# Debug_Phantom.net
KiCad netlist of a schematic drawn in EAGLE
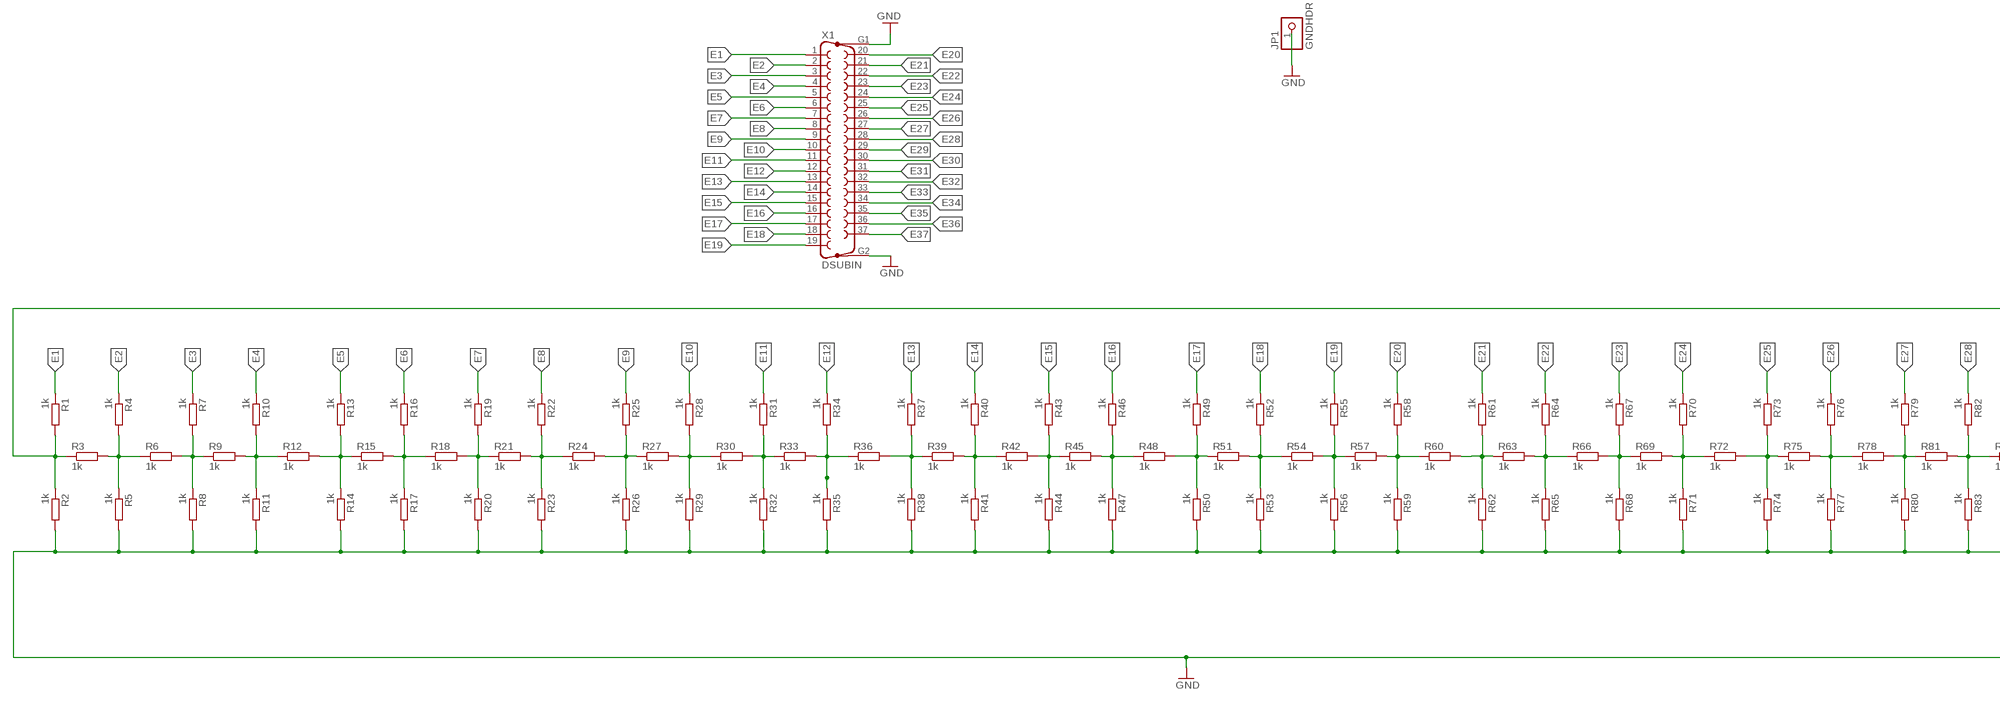
[diagram p0: schematic, sheet 1, part 1 of 2]
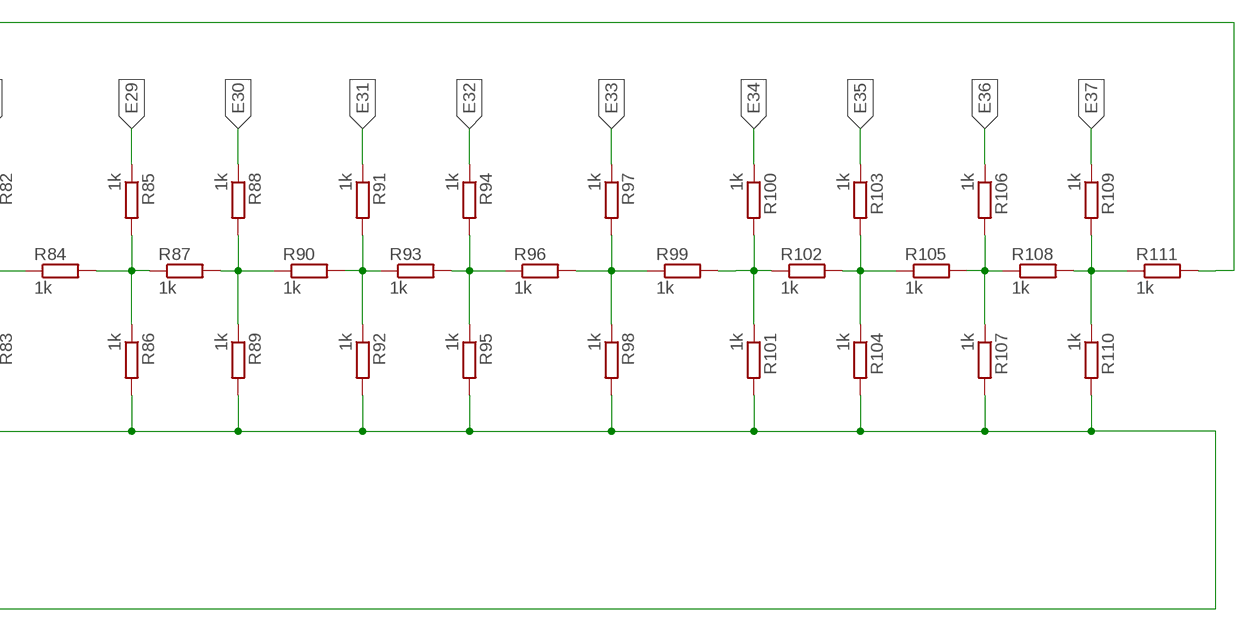
[diagram p1: schematic, sheet 1, part 2 of 2]

(export (version "E")
  (design (tool "Eeschema 10.0.6"))
  (components
    (comp (ref "JP1")
      (value "GNDHDR")
      (footprint "eagle-import:1X01")
      (libsource (lib "eagle-import") (part "PINHD-1X1"))
    )
    (comp (ref "R1")
      (value "1k")
      (footprint "eagle-import:R0402")
      (libsource (lib "eagle-import") (part "R-EU_R0402"))
    )
    (comp (ref "R2")
      (value "1k")
      (footprint "eagle-import:R0402")
      (libsource (lib "eagle-import") (part "R-EU_R0402"))
    )
    (comp (ref "R3")
      (value "1k")
      (footprint "eagle-import:R0402")
      (libsource (lib "eagle-import") (part "R-EU_R0402"))
    )
    (comp (ref "R4")
      (value "1k")
      (footprint "eagle-import:R0402")
      (libsource (lib "eagle-import") (part "R-EU_R0402"))
    )
    (comp (ref "R5")
      (value "1k")
      (footprint "eagle-import:R0402")
      (libsource (lib "eagle-import") (part "R-EU_R0402"))
    )
    (comp (ref "R6")
      (value "1k")
      (footprint "eagle-import:R0402")
      (libsource (lib "eagle-import") (part "R-EU_R0402"))
    )
    (comp (ref "R7")
      (value "1k")
      (footprint "eagle-import:R0402")
      (libsource (lib "eagle-import") (part "R-EU_R0402"))
    )
    (comp (ref "R8")
      (value "1k")
      (footprint "eagle-import:R0402")
      (libsource (lib "eagle-import") (part "R-EU_R0402"))
    )
    (comp (ref "R9")
      (value "1k")
      (footprint "eagle-import:R0402")
      (libsource (lib "eagle-import") (part "R-EU_R0402"))
    )
    (comp (ref "R10")
      (value "1k")
      (footprint "eagle-import:R0402")
      (libsource (lib "eagle-import") (part "R-EU_R0402"))
    )
    (comp (ref "R11")
      (value "1k")
      (footprint "eagle-import:R0402")
      (libsource (lib "eagle-import") (part "R-EU_R0402"))
    )
    (comp (ref "R12")
      (value "1k")
      (footprint "eagle-import:R0402")
      (libsource (lib "eagle-import") (part "R-EU_R0402"))
    )
    (comp (ref "R13")
      (value "1k")
      (footprint "eagle-import:R0402")
      (libsource (lib "eagle-import") (part "R-EU_R0402"))
    )
    (comp (ref "R14")
      (value "1k")
      (footprint "eagle-import:R0402")
      (libsource (lib "eagle-import") (part "R-EU_R0402"))
    )
    (comp (ref "R15")
      (value "1k")
      (footprint "eagle-import:R0402")
      (libsource (lib "eagle-import") (part "R-EU_R0402"))
    )
    (comp (ref "R16")
      (value "1k")
      (footprint "eagle-import:R0402")
      (libsource (lib "eagle-import") (part "R-EU_R0402"))
    )
    (comp (ref "R17")
      (value "1k")
      (footprint "eagle-import:R0402")
      (libsource (lib "eagle-import") (part "R-EU_R0402"))
    )
    (comp (ref "R18")
      (value "1k")
      (footprint "eagle-import:R0402")
      (libsource (lib "eagle-import") (part "R-EU_R0402"))
    )
    (comp (ref "R19")
      (value "1k")
      (footprint "eagle-import:R0402")
      (libsource (lib "eagle-import") (part "R-EU_R0402"))
    )
    (comp (ref "R20")
      (value "1k")
      (footprint "eagle-import:R0402")
      (libsource (lib "eagle-import") (part "R-EU_R0402"))
    )
    (comp (ref "R21")
      (value "1k")
      (footprint "eagle-import:R0402")
      (libsource (lib "eagle-import") (part "R-EU_R0402"))
    )
    (comp (ref "R22")
      (value "1k")
      (footprint "eagle-import:R0402")
      (libsource (lib "eagle-import") (part "R-EU_R0402"))
    )
    (comp (ref "R23")
      (value "1k")
      (footprint "eagle-import:R0402")
      (libsource (lib "eagle-import") (part "R-EU_R0402"))
    )
    (comp (ref "R24")
      (value "1k")
      (footprint "eagle-import:R0402")
      (libsource (lib "eagle-import") (part "R-EU_R0402"))
    )
    (comp (ref "R25")
      (value "1k")
      (footprint "eagle-import:R0402")
      (libsource (lib "eagle-import") (part "R-EU_R0402"))
    )
    (comp (ref "R26")
      (value "1k")
      (footprint "eagle-import:R0402")
      (libsource (lib "eagle-import") (part "R-EU_R0402"))
    )
    (comp (ref "R27")
      (value "1k")
      (footprint "eagle-import:R0402")
      (libsource (lib "eagle-import") (part "R-EU_R0402"))
    )
    (comp (ref "R28")
      (value "1k")
      (footprint "eagle-import:R0402")
      (libsource (lib "eagle-import") (part "R-EU_R0402"))
    )
    (comp (ref "R29")
      (value "1k")
      (footprint "eagle-import:R0402")
      (libsource (lib "eagle-import") (part "R-EU_R0402"))
    )
    (comp (ref "R30")
      (value "1k")
      (footprint "eagle-import:R0402")
      (libsource (lib "eagle-import") (part "R-EU_R0402"))
    )
    (comp (ref "R31")
      (value "1k")
      (footprint "eagle-import:R0402")
      (libsource (lib "eagle-import") (part "R-EU_R0402"))
    )
    (comp (ref "R32")
      (value "1k")
      (footprint "eagle-import:R0402")
      (libsource (lib "eagle-import") (part "R-EU_R0402"))
    )
    (comp (ref "R33")
      (value "1k")
      (footprint "eagle-import:R0402")
      (libsource (lib "eagle-import") (part "R-EU_R0402"))
    )
    (comp (ref "R34")
      (value "1k")
      (footprint "eagle-import:R0402")
      (libsource (lib "eagle-import") (part "R-EU_R0402"))
    )
    (comp (ref "R35")
      (value "1k")
      (footprint "eagle-import:R0402")
      (libsource (lib "eagle-import") (part "R-EU_R0402"))
    )
    (comp (ref "R36")
      (value "1k")
      (footprint "eagle-import:R0402")
      (libsource (lib "eagle-import") (part "R-EU_R0402"))
    )
    (comp (ref "R37")
      (value "1k")
      (footprint "eagle-import:R0402")
      (libsource (lib "eagle-import") (part "R-EU_R0402"))
    )
    (comp (ref "R38")
      (value "1k")
      (footprint "eagle-import:R0402")
      (libsource (lib "eagle-import") (part "R-EU_R0402"))
    )
    (comp (ref "R39")
      (value "1k")
      (footprint "eagle-import:R0402")
      (libsource (lib "eagle-import") (part "R-EU_R0402"))
    )
    (comp (ref "R40")
      (value "1k")
      (footprint "eagle-import:R0402")
      (libsource (lib "eagle-import") (part "R-EU_R0402"))
    )
    (comp (ref "R41")
      (value "1k")
      (footprint "eagle-import:R0402")
      (libsource (lib "eagle-import") (part "R-EU_R0402"))
    )
    (comp (ref "R42")
      (value "1k")
      (footprint "eagle-import:R0402")
      (libsource (lib "eagle-import") (part "R-EU_R0402"))
    )
    (comp (ref "R43")
      (value "1k")
      (footprint "eagle-import:R0402")
      (libsource (lib "eagle-import") (part "R-EU_R0402"))
    )
    (comp (ref "R44")
      (value "1k")
      (footprint "eagle-import:R0402")
      (libsource (lib "eagle-import") (part "R-EU_R0402"))
    )
    (comp (ref "R45")
      (value "1k")
      (footprint "eagle-import:R0402")
      (libsource (lib "eagle-import") (part "R-EU_R0402"))
    )
    (comp (ref "R46")
      (value "1k")
      (footprint "eagle-import:R0402")
      (libsource (lib "eagle-import") (part "R-EU_R0402"))
    )
    (comp (ref "R47")
      (value "1k")
      (footprint "eagle-import:R0402")
      (libsource (lib "eagle-import") (part "R-EU_R0402"))
    )
    (comp (ref "R48")
      (value "1k")
      (footprint "eagle-import:R0402")
      (libsource (lib "eagle-import") (part "R-EU_R0402"))
    )
    (comp (ref "R49")
      (value "1k")
      (footprint "eagle-import:R0402")
      (libsource (lib "eagle-import") (part "R-EU_R0402"))
    )
    (comp (ref "R50")
      (value "1k")
      (footprint "eagle-import:R0402")
      (libsource (lib "eagle-import") (part "R-EU_R0402"))
    )
    (comp (ref "R51")
      (value "1k")
      (footprint "eagle-import:R0402")
      (libsource (lib "eagle-import") (part "R-EU_R0402"))
    )
    (comp (ref "R52")
      (value "1k")
      (footprint "eagle-import:R0402")
      (libsource (lib "eagle-import") (part "R-EU_R0402"))
    )
    (comp (ref "R53")
      (value "1k")
      (footprint "eagle-import:R0402")
      (libsource (lib "eagle-import") (part "R-EU_R0402"))
    )
    (comp (ref "R54")
      (value "1k")
      (footprint "eagle-import:R0402")
      (libsource (lib "eagle-import") (part "R-EU_R0402"))
    )
    (comp (ref "R55")
      (value "1k")
      (footprint "eagle-import:R0402")
      (libsource (lib "eagle-import") (part "R-EU_R0402"))
    )
    (comp (ref "R56")
      (value "1k")
      (footprint "eagle-import:R0402")
      (libsource (lib "eagle-import") (part "R-EU_R0402"))
    )
    (comp (ref "R57")
      (value "1k")
      (footprint "eagle-import:R0402")
      (libsource (lib "eagle-import") (part "R-EU_R0402"))
    )
    (comp (ref "R58")
      (value "1k")
      (footprint "eagle-import:R0402")
      (libsource (lib "eagle-import") (part "R-EU_R0402"))
    )
    (comp (ref "R59")
      (value "1k")
      (footprint "eagle-import:R0402")
      (libsource (lib "eagle-import") (part "R-EU_R0402"))
    )
    (comp (ref "R60")
      (value "1k")
      (footprint "eagle-import:R0402")
      (libsource (lib "eagle-import") (part "R-EU_R0402"))
    )
    (comp (ref "R61")
      (value "1k")
      (footprint "eagle-import:R0402")
      (libsource (lib "eagle-import") (part "R-EU_R0402"))
    )
    (comp (ref "R62")
      (value "1k")
      (footprint "eagle-import:R0402")
      (libsource (lib "eagle-import") (part "R-EU_R0402"))
    )
    (comp (ref "R63")
      (value "1k")
      (footprint "eagle-import:R0402")
      (libsource (lib "eagle-import") (part "R-EU_R0402"))
    )
    (comp (ref "R64")
      (value "1k")
      (footprint "eagle-import:R0402")
      (libsource (lib "eagle-import") (part "R-EU_R0402"))
    )
    (comp (ref "R65")
      (value "1k")
      (footprint "eagle-import:R0402")
      (libsource (lib "eagle-import") (part "R-EU_R0402"))
    )
    (comp (ref "R66")
      (value "1k")
      (footprint "eagle-import:R0402")
      (libsource (lib "eagle-import") (part "R-EU_R0402"))
    )
    (comp (ref "R67")
      (value "1k")
      (footprint "eagle-import:R0402")
      (libsource (lib "eagle-import") (part "R-EU_R0402"))
    )
    (comp (ref "R68")
      (value "1k")
      (footprint "eagle-import:R0402")
      (libsource (lib "eagle-import") (part "R-EU_R0402"))
    )
    (comp (ref "R69")
      (value "1k")
      (footprint "eagle-import:R0402")
      (libsource (lib "eagle-import") (part "R-EU_R0402"))
    )
    (comp (ref "R70")
      (value "1k")
      (footprint "eagle-import:R0402")
      (libsource (lib "eagle-import") (part "R-EU_R0402"))
    )
    (comp (ref "R71")
      (value "1k")
      (footprint "eagle-import:R0402")
      (libsource (lib "eagle-import") (part "R-EU_R0402"))
    )
    (comp (ref "R72")
      (value "1k")
      (footprint "eagle-import:R0402")
      (libsource (lib "eagle-import") (part "R-EU_R0402"))
    )
    (comp (ref "R73")
      (value "1k")
      (footprint "eagle-import:R0402")
      (libsource (lib "eagle-import") (part "R-EU_R0402"))
    )
    (comp (ref "R74")
      (value "1k")
      (footprint "eagle-import:R0402")
      (libsource (lib "eagle-import") (part "R-EU_R0402"))
    )
    (comp (ref "R75")
      (value "1k")
      (footprint "eagle-import:R0402")
      (libsource (lib "eagle-import") (part "R-EU_R0402"))
    )
    (comp (ref "R76")
      (value "1k")
      (footprint "eagle-import:R0402")
      (libsource (lib "eagle-import") (part "R-EU_R0402"))
    )
    (comp (ref "R77")
      (value "1k")
      (footprint "eagle-import:R0402")
      (libsource (lib "eagle-import") (part "R-EU_R0402"))
    )
    (comp (ref "R78")
      (value "1k")
      (footprint "eagle-import:R0402")
      (libsource (lib "eagle-import") (part "R-EU_R0402"))
    )
    (comp (ref "R79")
      (value "1k")
      (footprint "eagle-import:R0402")
      (libsource (lib "eagle-import") (part "R-EU_R0402"))
    )
    (comp (ref "R80")
      (value "1k")
      (footprint "eagle-import:R0402")
      (libsource (lib "eagle-import") (part "R-EU_R0402"))
    )
    (comp (ref "R81")
      (value "1k")
      (footprint "eagle-import:R0402")
      (libsource (lib "eagle-import") (part "R-EU_R0402"))
    )
    (comp (ref "R82")
      (value "1k")
      (footprint "eagle-import:R0402")
      (libsource (lib "eagle-import") (part "R-EU_R0402"))
    )
    (comp (ref "R83")
      (value "1k")
      (footprint "eagle-import:R0402")
      (libsource (lib "eagle-import") (part "R-EU_R0402"))
    )
    (comp (ref "R84")
      (value "1k")
      (footprint "eagle-import:R0402")
      (libsource (lib "eagle-import") (part "R-EU_R0402"))
    )
    (comp (ref "R85")
      (value "1k")
      (footprint "eagle-import:R0402")
      (libsource (lib "eagle-import") (part "R-EU_R0402"))
    )
    (comp (ref "R86")
      (value "1k")
      (footprint "eagle-import:R0402")
      (libsource (lib "eagle-import") (part "R-EU_R0402"))
    )
    (comp (ref "R87")
      (value "1k")
      (footprint "eagle-import:R0402")
      (libsource (lib "eagle-import") (part "R-EU_R0402"))
    )
    (comp (ref "R88")
      (value "1k")
      (footprint "eagle-import:R0402")
      (libsource (lib "eagle-import") (part "R-EU_R0402"))
    )
    (comp (ref "R89")
      (value "1k")
      (footprint "eagle-import:R0402")
      (libsource (lib "eagle-import") (part "R-EU_R0402"))
    )
    (comp (ref "R90")
      (value "1k")
      (footprint "eagle-import:R0402")
      (libsource (lib "eagle-import") (part "R-EU_R0402"))
    )
    (comp (ref "R91")
      (value "1k")
      (footprint "eagle-import:R0402")
      (libsource (lib "eagle-import") (part "R-EU_R0402"))
    )
    (comp (ref "R92")
      (value "1k")
      (footprint "eagle-import:R0402")
      (libsource (lib "eagle-import") (part "R-EU_R0402"))
    )
    (comp (ref "R93")
      (value "1k")
      (footprint "eagle-import:R0402")
      (libsource (lib "eagle-import") (part "R-EU_R0402"))
    )
    (comp (ref "R94")
      (value "1k")
      (footprint "eagle-import:R0402")
      (libsource (lib "eagle-import") (part "R-EU_R0402"))
    )
    (comp (ref "R95")
      (value "1k")
      (footprint "eagle-import:R0402")
      (libsource (lib "eagle-import") (part "R-EU_R0402"))
    )
    (comp (ref "R96")
      (value "1k")
      (footprint "eagle-import:R0402")
      (libsource (lib "eagle-import") (part "R-EU_R0402"))
    )
    (comp (ref "R97")
      (value "1k")
      (footprint "eagle-import:R0402")
      (libsource (lib "eagle-import") (part "R-EU_R0402"))
    )
    (comp (ref "R98")
      (value "1k")
      (footprint "eagle-import:R0402")
      (libsource (lib "eagle-import") (part "R-EU_R0402"))
    )
    (comp (ref "R99")
      (value "1k")
      (footprint "eagle-import:R0402")
      (libsource (lib "eagle-import") (part "R-EU_R0402"))
    )
    (comp (ref "R100")
      (value "1k")
      (footprint "eagle-import:R0402")
      (libsource (lib "eagle-import") (part "R-EU_R0402"))
    )
    (comp (ref "R101")
      (value "1k")
      (footprint "eagle-import:R0402")
      (libsource (lib "eagle-import") (part "R-EU_R0402"))
    )
    (comp (ref "R102")
      (value "1k")
      (footprint "eagle-import:R0402")
      (libsource (lib "eagle-import") (part "R-EU_R0402"))
    )
    (comp (ref "R103")
      (value "1k")
      (footprint "eagle-import:R0402")
      (libsource (lib "eagle-import") (part "R-EU_R0402"))
    )
    (comp (ref "R104")
      (value "1k")
      (footprint "eagle-import:R0402")
      (libsource (lib "eagle-import") (part "R-EU_R0402"))
    )
    (comp (ref "R105")
      (value "1k")
      (footprint "eagle-import:R0402")
      (libsource (lib "eagle-import") (part "R-EU_R0402"))
    )
    (comp (ref "R106")
      (value "1k")
      (footprint "eagle-import:R0402")
      (libsource (lib "eagle-import") (part "R-EU_R0402"))
    )
    (comp (ref "R107")
      (value "1k")
      (footprint "eagle-import:R0402")
      (libsource (lib "eagle-import") (part "R-EU_R0402"))
    )
    (comp (ref "R108")
      (value "1k")
      (footprint "eagle-import:R0402")
      (libsource (lib "eagle-import") (part "R-EU_R0402"))
    )
    (comp (ref "R109")
      (value "1k")
      (footprint "eagle-import:R0402")
      (libsource (lib "eagle-import") (part "R-EU_R0402"))
    )
    (comp (ref "R110")
      (value "1k")
      (footprint "eagle-import:R0402")
      (libsource (lib "eagle-import") (part "R-EU_R0402"))
    )
    (comp (ref "R111")
      (value "1k")
      (footprint "eagle-import:R0402")
      (libsource (lib "eagle-import") (part "R-EU_R0402"))
    )
    (comp (ref "X1")
      (value "DSUBIN")
      (footprint "eagle-import:F37VP")
      (libsource (lib "eagle-import") (part "F37VP"))
    )
  )
  (nets
    (net (code "1") (name "E1") (class "Default")
      (node (ref "R1") (pin "1") (pinfunction "1_1") (pintype "passive"))
      (node (ref "X1") (pin "1") (pinfunction "1_1") (pintype "passive"))
    )
    (net (code "2") (name "E2") (class "Default")
      (node (ref "R4") (pin "1") (pinfunction "1_1") (pintype "passive"))
      (node (ref "X1") (pin "2") (pinfunction "2_2") (pintype "passive"))
    )
    (net (code "3") (name "E3") (class "Default")
      (node (ref "R7") (pin "1") (pinfunction "1_1") (pintype "passive"))
      (node (ref "X1") (pin "3") (pinfunction "3_3") (pintype "passive"))
    )
    (net (code "4") (name "E4") (class "Default")
      (node (ref "R10") (pin "1") (pinfunction "1_1") (pintype "passive"))
      (node (ref "X1") (pin "4") (pinfunction "4_4") (pintype "passive"))
    )
    (net (code "5") (name "E5") (class "Default")
      (node (ref "R13") (pin "1") (pinfunction "1_1") (pintype "passive"))
      (node (ref "X1") (pin "5") (pinfunction "5_5") (pintype "passive"))
    )
    (net (code "6") (name "E6") (class "Default")
      (node (ref "R16") (pin "1") (pinfunction "1_1") (pintype "passive"))
      (node (ref "X1") (pin "6") (pinfunction "6_6") (pintype "passive"))
    )
    (net (code "7") (name "E7") (class "Default")
      (node (ref "R19") (pin "1") (pinfunction "1_1") (pintype "passive"))
      (node (ref "X1") (pin "7") (pinfunction "7_7") (pintype "passive"))
    )
    (net (code "8") (name "E8") (class "Default")
      (node (ref "R22") (pin "1") (pinfunction "1_1") (pintype "passive"))
      (node (ref "X1") (pin "8") (pinfunction "8_8") (pintype "passive"))
    )
    (net (code "9") (name "E9") (class "Default")
      (node (ref "R25") (pin "1") (pinfunction "1_1") (pintype "passive"))
      (node (ref "X1") (pin "9") (pinfunction "9_9") (pintype "passive"))
    )
    (net (code "10") (name "E10") (class "Default")
      (node (ref "R28") (pin "1") (pinfunction "1_1") (pintype "passive"))
      (node (ref "X1") (pin "10") (pinfunction "10_10") (pintype "passive"))
    )
    (net (code "11") (name "E11") (class "Default")
      (node (ref "R31") (pin "1") (pinfunction "1_1") (pintype "passive"))
      (node (ref "X1") (pin "11") (pinfunction "11_11") (pintype "passive"))
    )
    (net (code "12") (name "E12") (class "Default")
      (node (ref "R34") (pin "1") (pinfunction "1_1") (pintype "passive"))
      (node (ref "X1") (pin "12") (pinfunction "12_12") (pintype "passive"))
    )
    (net (code "13") (name "E13") (class "Default")
      (node (ref "R37") (pin "1") (pinfunction "1_1") (pintype "passive"))
      (node (ref "X1") (pin "13") (pinfunction "13_13") (pintype "passive"))
    )
    (net (code "14") (name "E14") (class "Default")
      (node (ref "R40") (pin "1") (pinfunction "1_1") (pintype "passive"))
      (node (ref "X1") (pin "14") (pinfunction "14_14") (pintype "passive"))
    )
    (net (code "15") (name "E15") (class "Default")
      (node (ref "R43") (pin "1") (pinfunction "1_1") (pintype "passive"))
      (node (ref "X1") (pin "15") (pinfunction "15_15") (pintype "passive"))
    )
    (net (code "16") (name "E16") (class "Default")
      (node (ref "R46") (pin "1") (pinfunction "1_1") (pintype "passive"))
      (node (ref "X1") (pin "16") (pinfunction "16_16") (pintype "passive"))
    )
    (net (code "17") (name "E17") (class "Default")
      (node (ref "R49") (pin "1") (pinfunction "1_1") (pintype "passive"))
      (node (ref "X1") (pin "17") (pinfunction "17_17") (pintype "passive"))
    )
    (net (code "18") (name "E18") (class "Default")
      (node (ref "R52") (pin "1") (pinfunction "1_1") (pintype "passive"))
      (node (ref "X1") (pin "18") (pinfunction "18_18") (pintype "passive"))
    )
    (net (code "19") (name "E19") (class "Default")
      (node (ref "R55") (pin "1") (pinfunction "1_1") (pintype "passive"))
      (node (ref "X1") (pin "19") (pinfunction "19_19") (pintype "passive"))
    )
    (net (code "20") (name "E20") (class "Default")
      (node (ref "R58") (pin "1") (pinfunction "1_1") (pintype "passive"))
      (node (ref "X1") (pin "20") (pinfunction "20_20") (pintype "passive"))
    )
    (net (code "21") (name "E21") (class "Default")
      (node (ref "R61") (pin "1") (pinfunction "1_1") (pintype "passive"))
      (node (ref "X1") (pin "21") (pinfunction "21_21") (pintype "passive"))
    )
    (net (code "22") (name "E22") (class "Default")
      (node (ref "R64") (pin "1") (pinfunction "1_1") (pintype "passive"))
      (node (ref "X1") (pin "22") (pinfunction "22_22") (pintype "passive"))
    )
    (net (code "23") (name "E23") (class "Default")
      (node (ref "R67") (pin "1") (pinfunction "1_1") (pintype "passive"))
      (node (ref "X1") (pin "23") (pinfunction "23_23") (pintype "passive"))
    )
    (net (code "24") (name "E24") (class "Default")
      (node (ref "R70") (pin "1") (pinfunction "1_1") (pintype "passive"))
      (node (ref "X1") (pin "24") (pinfunction "24_24") (pintype "passive"))
    )
    (net (code "25") (name "E25") (class "Default")
      (node (ref "R73") (pin "1") (pinfunction "1_1") (pintype "passive"))
      (node (ref "X1") (pin "25") (pinfunction "25_25") (pintype "passive"))
    )
    (net (code "26") (name "E26") (class "Default")
      (node (ref "R76") (pin "1") (pinfunction "1_1") (pintype "passive"))
      (node (ref "X1") (pin "26") (pinfunction "26_26") (pintype "passive"))
    )
    (net (code "27") (name "E27") (class "Default")
      (node (ref "R79") (pin "1") (pinfunction "1_1") (pintype "passive"))
      (node (ref "X1") (pin "27") (pinfunction "27_27") (pintype "passive"))
    )
    (net (code "28") (name "E28") (class "Default")
      (node (ref "R82") (pin "1") (pinfunction "1_1") (pintype "passive"))
      (node (ref "X1") (pin "28") (pinfunction "28_28") (pintype "passive"))
    )
    (net (code "29") (name "E29") (class "Default")
      (node (ref "R85") (pin "1") (pinfunction "1_1") (pintype "passive"))
      (node (ref "X1") (pin "29") (pinfunction "29_29") (pintype "passive"))
    )
    (net (code "30") (name "E30") (class "Default")
      (node (ref "R88") (pin "1") (pinfunction "1_1") (pintype "passive"))
      (node (ref "X1") (pin "30") (pinfunction "30_30") (pintype "passive"))
    )
    (net (code "31") (name "E31") (class "Default")
      (node (ref "R91") (pin "1") (pinfunction "1_1") (pintype "passive"))
      (node (ref "X1") (pin "31") (pinfunction "31_31") (pintype "passive"))
    )
    (net (code "32") (name "E32") (class "Default")
      (node (ref "R94") (pin "1") (pinfunction "1_1") (pintype "passive"))
      (node (ref "X1") (pin "32") (pinfunction "32_32") (pintype "passive"))
    )
    (net (code "33") (name "E33") (class "Default")
      (node (ref "R97") (pin "1") (pinfunction "1_1") (pintype "passive"))
      (node (ref "X1") (pin "33") (pinfunction "33_33") (pintype "passive"))
    )
    (net (code "34") (name "E34") (class "Default")
      (node (ref "R100") (pin "1") (pinfunction "1_1") (pintype "passive"))
      (node (ref "X1") (pin "34") (pinfunction "34_34") (pintype "passive"))
    )
    (net (code "35") (name "E35") (class "Default")
      (node (ref "R103") (pin "1") (pinfunction "1_1") (pintype "passive"))
      (node (ref "X1") (pin "35") (pinfunction "35_35") (pintype "passive"))
    )
    (net (code "36") (name "E36") (class "Default")
      (node (ref "R106") (pin "1") (pinfunction "1_1") (pintype "passive"))
      (node (ref "X1") (pin "36") (pinfunction "36_36") (pintype "passive"))
    )
    (net (code "37") (name "E37") (class "Default")
      (node (ref "R109") (pin "1") (pinfunction "1_1") (pintype "passive"))
      (node (ref "X1") (pin "37") (pinfunction "37_37") (pintype "passive"))
    )
    (net (code "38") (name "GND") (class "Default")
      (node (ref "JP1") (pin "1") (pinfunction "1_1") (pintype "passive"))
      (node (ref "R101") (pin "2") (pinfunction "2_2") (pintype "passive"))
      (node (ref "R104") (pin "2") (pinfunction "2_2") (pintype "passive"))
      (node (ref "R107") (pin "2") (pinfunction "2_2") (pintype "passive"))
      (node (ref "R11") (pin "2") (pinfunction "2_2") (pintype "passive"))
      (node (ref "R110") (pin "2") (pinfunction "2_2") (pintype "passive"))
      (node (ref "R14") (pin "2") (pinfunction "2_2") (pintype "passive"))
      (node (ref "R17") (pin "2") (pinfunction "2_2") (pintype "passive"))
      (node (ref "R2") (pin "2") (pinfunction "2_2") (pintype "passive"))
      (node (ref "R20") (pin "2") (pinfunction "2_2") (pintype "passive"))
      (node (ref "R23") (pin "2") (pinfunction "2_2") (pintype "passive"))
      (node (ref "R26") (pin "2") (pinfunction "2_2") (pintype "passive"))
      (node (ref "R29") (pin "2") (pinfunction "2_2") (pintype "passive"))
      (node (ref "R32") (pin "2") (pinfunction "2_2") (pintype "passive"))
      (node (ref "R35") (pin "2") (pinfunction "2_2") (pintype "passive"))
      (node (ref "R38") (pin "2") (pinfunction "2_2") (pintype "passive"))
      (node (ref "R41") (pin "2") (pinfunction "2_2") (pintype "passive"))
      (node (ref "R44") (pin "2") (pinfunction "2_2") (pintype "passive"))
      (node (ref "R47") (pin "2") (pinfunction "2_2") (pintype "passive"))
      (node (ref "R5") (pin "2") (pinfunction "2_2") (pintype "passive"))
      (node (ref "R50") (pin "2") (pinfunction "2_2") (pintype "passive"))
      (node (ref "R53") (pin "2") (pinfunction "2_2") (pintype "passive"))
      (node (ref "R56") (pin "2") (pinfunction "2_2") (pintype "passive"))
      (node (ref "R59") (pin "2") (pinfunction "2_2") (pintype "passive"))
      (node (ref "R62") (pin "2") (pinfunction "2_2") (pintype "passive"))
      (node (ref "R65") (pin "2") (pinfunction "2_2") (pintype "passive"))
      (node (ref "R68") (pin "2") (pinfunction "2_2") (pintype "passive"))
      (node (ref "R71") (pin "2") (pinfunction "2_2") (pintype "passive"))
      (node (ref "R74") (pin "2") (pinfunction "2_2") (pintype "passive"))
      (node (ref "R77") (pin "2") (pinfunction "2_2") (pintype "passive"))
      (node (ref "R8") (pin "2") (pinfunction "2_2") (pintype "passive"))
      (node (ref "R80") (pin "2") (pinfunction "2_2") (pintype "passive"))
      (node (ref "R83") (pin "2") (pinfunction "2_2") (pintype "passive"))
      (node (ref "R86") (pin "2") (pinfunction "2_2") (pintype "passive"))
      (node (ref "R89") (pin "2") (pinfunction "2_2") (pintype "passive"))
      (node (ref "R92") (pin "2") (pinfunction "2_2") (pintype "passive"))
      (node (ref "R95") (pin "2") (pinfunction "2_2") (pintype "passive"))
      (node (ref "R98") (pin "2") (pinfunction "2_2") (pintype "passive"))
      (node (ref "X1") (pin "G1") (pinfunction "G1_G1") (pintype "passive"))
      (node (ref "X1") (pin "G2") (pinfunction "G2_G2") (pintype "passive"))
    )
    (net (code "39") (name "Net-(R1-Pad2)") (class "Default")
      (node (ref "R1") (pin "2") (pinfunction "2_2") (pintype "passive"))
      (node (ref "R111") (pin "2") (pinfunction "2_2") (pintype "passive"))
      (node (ref "R2") (pin "1") (pinfunction "1_1") (pintype "passive"))
      (node (ref "R3") (pin "1") (pinfunction "1_1") (pintype "passive"))
    )
    (net (code "40") (name "Net-(R3-Pad2)") (class "Default")
      (node (ref "R3") (pin "2") (pinfunction "2_2") (pintype "passive"))
      (node (ref "R4") (pin "2") (pinfunction "2_2") (pintype "passive"))
      (node (ref "R5") (pin "1") (pinfunction "1_1") (pintype "passive"))
      (node (ref "R6") (pin "1") (pinfunction "1_1") (pintype "passive"))
    )
    (net (code "41") (name "Net-(R6-Pad2)") (class "Default")
      (node (ref "R6") (pin "2") (pinfunction "2_2") (pintype "passive"))
      (node (ref "R7") (pin "2") (pinfunction "2_2") (pintype "passive"))
      (node (ref "R8") (pin "1") (pinfunction "1_1") (pintype "passive"))
      (node (ref "R9") (pin "1") (pinfunction "1_1") (pintype "passive"))
    )
    (net (code "42") (name "Net-(R10-Pad2)") (class "Default")
      (node (ref "R10") (pin "2") (pinfunction "2_2") (pintype "passive"))
      (node (ref "R11") (pin "1") (pinfunction "1_1") (pintype "passive"))
      (node (ref "R12") (pin "1") (pinfunction "1_1") (pintype "passive"))
      (node (ref "R9") (pin "2") (pinfunction "2_2") (pintype "passive"))
    )
    (net (code "43") (name "Net-(R12-Pad2)") (class "Default")
      (node (ref "R12") (pin "2") (pinfunction "2_2") (pintype "passive"))
      (node (ref "R13") (pin "2") (pinfunction "2_2") (pintype "passive"))
      (node (ref "R14") (pin "1") (pinfunction "1_1") (pintype "passive"))
      (node (ref "R15") (pin "1") (pinfunction "1_1") (pintype "passive"))
    )
    (net (code "44") (name "Net-(R15-Pad2)") (class "Default")
      (node (ref "R15") (pin "2") (pinfunction "2_2") (pintype "passive"))
      (node (ref "R16") (pin "2") (pinfunction "2_2") (pintype "passive"))
      (node (ref "R17") (pin "1") (pinfunction "1_1") (pintype "passive"))
      (node (ref "R18") (pin "1") (pinfunction "1_1") (pintype "passive"))
    )
    (net (code "45") (name "Net-(R18-Pad2)") (class "Default")
      (node (ref "R18") (pin "2") (pinfunction "2_2") (pintype "passive"))
      (node (ref "R19") (pin "2") (pinfunction "2_2") (pintype "passive"))
      (node (ref "R20") (pin "1") (pinfunction "1_1") (pintype "passive"))
      (node (ref "R21") (pin "1") (pinfunction "1_1") (pintype "passive"))
    )
    (net (code "46") (name "Net-(R21-Pad2)") (class "Default")
      (node (ref "R21") (pin "2") (pinfunction "2_2") (pintype "passive"))
      (node (ref "R22") (pin "2") (pinfunction "2_2") (pintype "passive"))
      (node (ref "R23") (pin "1") (pinfunction "1_1") (pintype "passive"))
      (node (ref "R24") (pin "1") (pinfunction "1_1") (pintype "passive"))
    )
    (net (code "47") (name "Net-(R24-Pad2)") (class "Default")
      (node (ref "R24") (pin "2") (pinfunction "2_2") (pintype "passive"))
      (node (ref "R25") (pin "2") (pinfunction "2_2") (pintype "passive"))
      (node (ref "R26") (pin "1") (pinfunction "1_1") (pintype "passive"))
      (node (ref "R27") (pin "1") (pinfunction "1_1") (pintype "passive"))
    )
    (net (code "48") (name "Net-(R27-Pad2)") (class "Default")
      (node (ref "R27") (pin "2") (pinfunction "2_2") (pintype "passive"))
      (node (ref "R28") (pin "2") (pinfunction "2_2") (pintype "passive"))
      (node (ref "R29") (pin "1") (pinfunction "1_1") (pintype "passive"))
      (node (ref "R30") (pin "1") (pinfunction "1_1") (pintype "passive"))
    )
    (net (code "49") (name "Net-(R30-Pad2)") (class "Default")
      (node (ref "R30") (pin "2") (pinfunction "2_2") (pintype "passive"))
      (node (ref "R31") (pin "2") (pinfunction "2_2") (pintype "passive"))
      (node (ref "R32") (pin "1") (pinfunction "1_1") (pintype "passive"))
      (node (ref "R33") (pin "1") (pinfunction "1_1") (pintype "passive"))
    )
    (net (code "50") (name "Net-(R33-Pad2)") (class "Default")
      (node (ref "R33") (pin "2") (pinfunction "2_2") (pintype "passive"))
      (node (ref "R34") (pin "2") (pinfunction "2_2") (pintype "passive"))
      (node (ref "R35") (pin "1") (pinfunction "1_1") (pintype "passive"))
      (node (ref "R36") (pin "1") (pinfunction "1_1") (pintype "passive"))
    )
    (net (code "51") (name "Net-(R36-Pad2)") (class "Default")
      (node (ref "R36") (pin "2") (pinfunction "2_2") (pintype "passive"))
      (node (ref "R37") (pin "2") (pinfunction "2_2") (pintype "passive"))
      (node (ref "R38") (pin "1") (pinfunction "1_1") (pintype "passive"))
      (node (ref "R39") (pin "1") (pinfunction "1_1") (pintype "passive"))
    )
    (net (code "52") (name "Net-(R39-Pad2)") (class "Default")
      (node (ref "R39") (pin "2") (pinfunction "2_2") (pintype "passive"))
      (node (ref "R40") (pin "2") (pinfunction "2_2") (pintype "passive"))
      (node (ref "R41") (pin "1") (pinfunction "1_1") (pintype "passive"))
      (node (ref "R42") (pin "1") (pinfunction "1_1") (pintype "passive"))
    )
    (net (code "53") (name "Net-(R42-Pad2)") (class "Default")
      (node (ref "R42") (pin "2") (pinfunction "2_2") (pintype "passive"))
      (node (ref "R43") (pin "2") (pinfunction "2_2") (pintype "passive"))
      (node (ref "R44") (pin "1") (pinfunction "1_1") (pintype "passive"))
      (node (ref "R45") (pin "1") (pinfunction "1_1") (pintype "passive"))
    )
    (net (code "54") (name "Net-(R45-Pad2)") (class "Default")
      (node (ref "R45") (pin "2") (pinfunction "2_2") (pintype "passive"))
      (node (ref "R46") (pin "2") (pinfunction "2_2") (pintype "passive"))
      (node (ref "R47") (pin "1") (pinfunction "1_1") (pintype "passive"))
      (node (ref "R48") (pin "1") (pinfunction "1_1") (pintype "passive"))
    )
    (net (code "55") (name "Net-(R48-Pad2)") (class "Default")
      (node (ref "R48") (pin "2") (pinfunction "2_2") (pintype "passive"))
      (node (ref "R49") (pin "2") (pinfunction "2_2") (pintype "passive"))
      (node (ref "R50") (pin "1") (pinfunction "1_1") (pintype "passive"))
      (node (ref "R51") (pin "1") (pinfunction "1_1") (pintype "passive"))
    )
    (net (code "56") (name "Net-(R51-Pad2)") (class "Default")
      (node (ref "R51") (pin "2") (pinfunction "2_2") (pintype "passive"))
      (node (ref "R52") (pin "2") (pinfunction "2_2") (pintype "passive"))
      (node (ref "R53") (pin "1") (pinfunction "1_1") (pintype "passive"))
      (node (ref "R54") (pin "1") (pinfunction "1_1") (pintype "passive"))
    )
    (net (code "57") (name "Net-(R54-Pad2)") (class "Default")
      (node (ref "R54") (pin "2") (pinfunction "2_2") (pintype "passive"))
      (node (ref "R55") (pin "2") (pinfunction "2_2") (pintype "passive"))
      (node (ref "R56") (pin "1") (pinfunction "1_1") (pintype "passive"))
      (node (ref "R57") (pin "1") (pinfunction "1_1") (pintype "passive"))
    )
    (net (code "58") (name "Net-(R57-Pad2)") (class "Default")
      (node (ref "R57") (pin "2") (pinfunction "2_2") (pintype "passive"))
      (node (ref "R58") (pin "2") (pinfunction "2_2") (pintype "passive"))
      (node (ref "R59") (pin "1") (pinfunction "1_1") (pintype "passive"))
      (node (ref "R60") (pin "1") (pinfunction "1_1") (pintype "passive"))
    )
    (net (code "59") (name "Net-(R60-Pad2)") (class "Default")
      (node (ref "R60") (pin "2") (pinfunction "2_2") (pintype "passive"))
      (node (ref "R61") (pin "2") (pinfunction "2_2") (pintype "passive"))
      (node (ref "R62") (pin "1") (pinfunction "1_1") (pintype "passive"))
      (node (ref "R63") (pin "1") (pinfunction "1_1") (pintype "passive"))
    )
    (net (code "60") (name "Net-(R63-Pad2)") (class "Default")
      (node (ref "R63") (pin "2") (pinfunction "2_2") (pintype "passive"))
      (node (ref "R64") (pin "2") (pinfunction "2_2") (pintype "passive"))
      (node (ref "R65") (pin "1") (pinfunction "1_1") (pintype "passive"))
      (node (ref "R66") (pin "1") (pinfunction "1_1") (pintype "passive"))
    )
    (net (code "61") (name "Net-(R66-Pad2)") (class "Default")
      (node (ref "R66") (pin "2") (pinfunction "2_2") (pintype "passive"))
      (node (ref "R67") (pin "2") (pinfunction "2_2") (pintype "passive"))
      (node (ref "R68") (pin "1") (pinfunction "1_1") (pintype "passive"))
      (node (ref "R69") (pin "1") (pinfunction "1_1") (pintype "passive"))
    )
    (net (code "62") (name "Net-(R69-Pad2)") (class "Default")
      (node (ref "R69") (pin "2") (pinfunction "2_2") (pintype "passive"))
      (node (ref "R70") (pin "2") (pinfunction "2_2") (pintype "passive"))
      (node (ref "R71") (pin "1") (pinfunction "1_1") (pintype "passive"))
      (node (ref "R72") (pin "1") (pinfunction "1_1") (pintype "passive"))
    )
    (net (code "63") (name "Net-(R72-Pad2)") (class "Default")
      (node (ref "R72") (pin "2") (pinfunction "2_2") (pintype "passive"))
      (node (ref "R73") (pin "2") (pinfunction "2_2") (pintype "passive"))
      (node (ref "R74") (pin "1") (pinfunction "1_1") (pintype "passive"))
      (node (ref "R75") (pin "1") (pinfunction "1_1") (pintype "passive"))
    )
    (net (code "64") (name "Net-(R75-Pad2)") (class "Default")
      (node (ref "R75") (pin "2") (pinfunction "2_2") (pintype "passive"))
      (node (ref "R76") (pin "2") (pinfunction "2_2") (pintype "passive"))
      (node (ref "R77") (pin "1") (pinfunction "1_1") (pintype "passive"))
      (node (ref "R78") (pin "1") (pinfunction "1_1") (pintype "passive"))
    )
    (net (code "65") (name "Net-(R78-Pad2)") (class "Default")
      (node (ref "R78") (pin "2") (pinfunction "2_2") (pintype "passive"))
      (node (ref "R79") (pin "2") (pinfunction "2_2") (pintype "passive"))
      (node (ref "R80") (pin "1") (pinfunction "1_1") (pintype "passive"))
      (node (ref "R81") (pin "1") (pinfunction "1_1") (pintype "passive"))
    )
    (net (code "66") (name "Net-(R81-Pad2)") (class "Default")
      (node (ref "R81") (pin "2") (pinfunction "2_2") (pintype "passive"))
      (node (ref "R82") (pin "2") (pinfunction "2_2") (pintype "passive"))
      (node (ref "R83") (pin "1") (pinfunction "1_1") (pintype "passive"))
      (node (ref "R84") (pin "1") (pinfunction "1_1") (pintype "passive"))
    )
    (net (code "67") (name "Net-(R84-Pad2)") (class "Default")
      (node (ref "R84") (pin "2") (pinfunction "2_2") (pintype "passive"))
      (node (ref "R85") (pin "2") (pinfunction "2_2") (pintype "passive"))
      (node (ref "R86") (pin "1") (pinfunction "1_1") (pintype "passive"))
      (node (ref "R87") (pin "1") (pinfunction "1_1") (pintype "passive"))
    )
    (net (code "68") (name "Net-(R87-Pad2)") (class "Default")
      (node (ref "R87") (pin "2") (pinfunction "2_2") (pintype "passive"))
      (node (ref "R88") (pin "2") (pinfunction "2_2") (pintype "passive"))
      (node (ref "R89") (pin "1") (pinfunction "1_1") (pintype "passive"))
      (node (ref "R90") (pin "1") (pinfunction "1_1") (pintype "passive"))
    )
    (net (code "69") (name "Net-(R90-Pad2)") (class "Default")
      (node (ref "R90") (pin "2") (pinfunction "2_2") (pintype "passive"))
      (node (ref "R91") (pin "2") (pinfunction "2_2") (pintype "passive"))
      (node (ref "R92") (pin "1") (pinfunction "1_1") (pintype "passive"))
      (node (ref "R93") (pin "1") (pinfunction "1_1") (pintype "passive"))
    )
    (net (code "70") (name "Net-(R93-Pad2)") (class "Default")
      (node (ref "R93") (pin "2") (pinfunction "2_2") (pintype "passive"))
      (node (ref "R94") (pin "2") (pinfunction "2_2") (pintype "passive"))
      (node (ref "R95") (pin "1") (pinfunction "1_1") (pintype "passive"))
      (node (ref "R96") (pin "1") (pinfunction "1_1") (pintype "passive"))
    )
    (net (code "71") (name "Net-(R96-Pad2)") (class "Default")
      (node (ref "R96") (pin "2") (pinfunction "2_2") (pintype "passive"))
      (node (ref "R97") (pin "2") (pinfunction "2_2") (pintype "passive"))
      (node (ref "R98") (pin "1") (pinfunction "1_1") (pintype "passive"))
      (node (ref "R99") (pin "1") (pinfunction "1_1") (pintype "passive"))
    )
    (net (code "72") (name "Net-(R100-Pad2)") (class "Default")
      (node (ref "R100") (pin "2") (pinfunction "2_2") (pintype "passive"))
      (node (ref "R101") (pin "1") (pinfunction "1_1") (pintype "passive"))
      (node (ref "R102") (pin "1") (pinfunction "1_1") (pintype "passive"))
      (node (ref "R99") (pin "2") (pinfunction "2_2") (pintype "passive"))
    )
    (net (code "73") (name "Net-(R102-Pad2)") (class "Default")
      (node (ref "R102") (pin "2") (pinfunction "2_2") (pintype "passive"))
      (node (ref "R103") (pin "2") (pinfunction "2_2") (pintype "passive"))
      (node (ref "R104") (pin "1") (pinfunction "1_1") (pintype "passive"))
      (node (ref "R105") (pin "1") (pinfunction "1_1") (pintype "passive"))
    )
    (net (code "74") (name "Net-(R105-Pad2)") (class "Default")
      (node (ref "R105") (pin "2") (pinfunction "2_2") (pintype "passive"))
      (node (ref "R106") (pin "2") (pinfunction "2_2") (pintype "passive"))
      (node (ref "R107") (pin "1") (pinfunction "1_1") (pintype "passive"))
      (node (ref "R108") (pin "1") (pinfunction "1_1") (pintype "passive"))
    )
    (net (code "75") (name "Net-(R108-Pad2)") (class "Default")
      (node (ref "R108") (pin "2") (pinfunction "2_2") (pintype "passive"))
      (node (ref "R109") (pin "2") (pinfunction "2_2") (pintype "passive"))
      (node (ref "R110") (pin "1") (pinfunction "1_1") (pintype "passive"))
      (node (ref "R111") (pin "1") (pinfunction "1_1") (pintype "passive"))
    )
  )
)
